# CurrentSense.net
KiCad netlist of a schematic drawn in Altium Designer
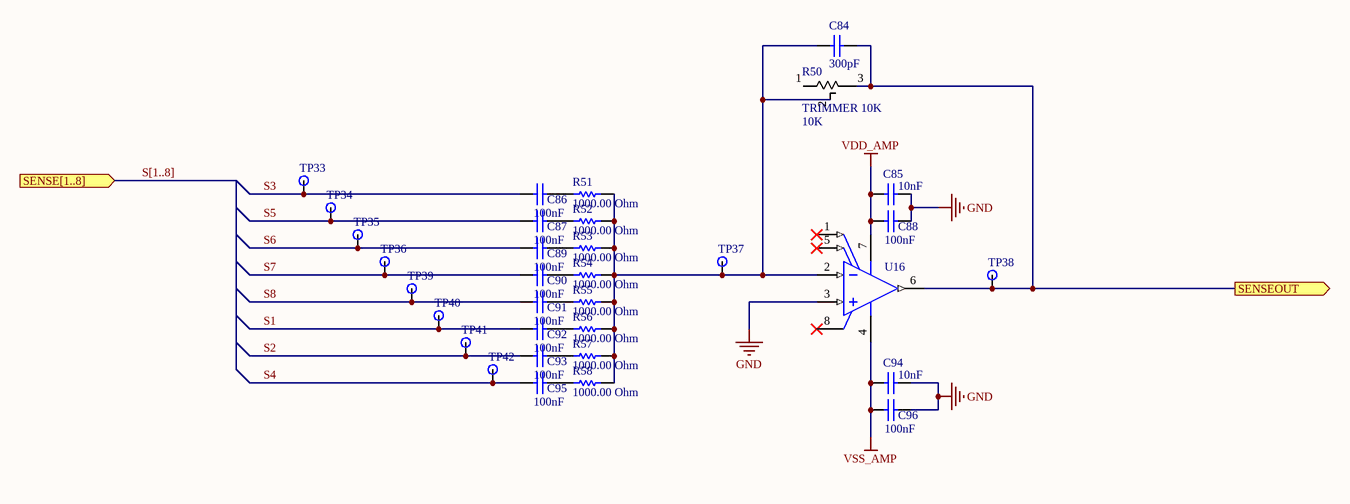
[diagram p0: CurrentSense.SchDoc]

(export (version "E")
  (design (tool "Eeschema 10.0.6"))
  (components
    (comp (ref "C84")
      (value "300pF")
      (footprint "CAPC0603(1608)100_N")
      (description "CAP 300pF 25V ±10% 0603 (1608 Metric) Thickness 1mm SMD")
      (fields (field (name "TOLERANCE") "Â±10%") (field (name "Comment") "CAP 300pF 25V 0603(1608)"))
      (libsource (lib "Altium Content Vault") (part "CMP-1035-01546-1"))
    )
    (comp (ref "C85")
      (value "10nF")
      (footprint "CAPC0603(1608)100_N")
      (description "CAP 10nF 25V ±10% 0603 (1608 Metric) Thickness 1mm SMD")
      (fields (field (name "TOLERANCE") "Â±10%") (field (name "Comment") "CAP 10nF 25V 0603(1608)"))
      (libsource (lib "Altium Content Vault") (part "CMP-1035-02317-1"))
    )
    (comp (ref "C86")
      (value "100nF")
      (footprint "CAPC0603(1608)100_M")
      (description "CAP 100nF 25V ±10% 0603 (1608 Metric) Thickness 1mm SMD")
      (fields (field (name "TOLERANCE") "Â±10%") (field (name "Comment") "CAP 100nF 25V 0603(1608)"))
      (libsource (lib "Altium Content Vault") (part "CMP-1035-02588-1"))
    )
    (comp (ref "C87")
      (value "100nF")
      (footprint "CAPC0603(1608)100_M")
      (description "CAP 100nF 25V ±10% 0603 (1608 Metric) Thickness 1mm SMD")
      (fields (field (name "TOLERANCE") "Â±10%") (field (name "Comment") "CAP 100nF 25V 0603(1608)"))
      (libsource (lib "Altium Content Vault") (part "CMP-1035-02588-1"))
    )
    (comp (ref "C88")
      (value "100nF")
      (footprint "CAPC0603(1608)100_M")
      (description "CAP 100nF 25V ±10% 0603 (1608 Metric) Thickness 1mm SMD")
      (fields (field (name "TOLERANCE") "Â±10%") (field (name "Comment") "CAP 100nF 25V 0603(1608)"))
      (libsource (lib "Altium Content Vault") (part "CMP-1035-02588-1"))
    )
    (comp (ref "C89")
      (value "100nF")
      (footprint "CAPC0603(1608)100_M")
      (description "CAP 100nF 25V ±10% 0603 (1608 Metric) Thickness 1mm SMD")
      (fields (field (name "TOLERANCE") "Â±10%") (field (name "Comment") "CAP 100nF 25V 0603(1608)"))
      (libsource (lib "Altium Content Vault") (part "CMP-1035-02588-1"))
    )
    (comp (ref "C90")
      (value "100nF")
      (footprint "CAPC0603(1608)100_M")
      (description "CAP 100nF 25V ±10% 0603 (1608 Metric) Thickness 1mm SMD")
      (fields (field (name "TOLERANCE") "Â±10%") (field (name "Comment") "CAP 100nF 25V 0603(1608)"))
      (libsource (lib "Altium Content Vault") (part "CMP-1035-02588-1"))
    )
    (comp (ref "C91")
      (value "100nF")
      (footprint "CAPC0603(1608)100_M")
      (description "CAP 100nF 25V ±10% 0603 (1608 Metric) Thickness 1mm SMD")
      (fields (field (name "TOLERANCE") "Â±10%") (field (name "Comment") "CAP 100nF 25V 0603(1608)"))
      (libsource (lib "Altium Content Vault") (part "CMP-1035-02588-1"))
    )
    (comp (ref "C92")
      (value "100nF")
      (footprint "CAPC0603(1608)100_M")
      (description "CAP 100nF 25V ±10% 0603 (1608 Metric) Thickness 1mm SMD")
      (fields (field (name "TOLERANCE") "Â±10%") (field (name "Comment") "CAP 100nF 25V 0603(1608)"))
      (libsource (lib "Altium Content Vault") (part "CMP-1035-02588-1"))
    )
    (comp (ref "C93")
      (value "100nF")
      (footprint "CAPC0603(1608)100_M")
      (description "CAP 100nF 25V ±10% 0603 (1608 Metric) Thickness 1mm SMD")
      (fields (field (name "TOLERANCE") "Â±10%") (field (name "Comment") "CAP 100nF 25V 0603(1608)"))
      (libsource (lib "Altium Content Vault") (part "CMP-1035-02588-1"))
    )
    (comp (ref "C94")
      (value "10nF")
      (footprint "CAPC0603(1608)100_N")
      (description "CAP 10nF 25V ±10% 0603 (1608 Metric) Thickness 1mm SMD")
      (fields (field (name "TOLERANCE") "Â±10%") (field (name "Comment") "CAP 10nF 25V 0603(1608)"))
      (libsource (lib "Altium Content Vault") (part "CMP-1035-02317-1"))
    )
    (comp (ref "C95")
      (value "100nF")
      (footprint "CAPC0603(1608)100_M")
      (description "CAP 100nF 25V ±10% 0603 (1608 Metric) Thickness 1mm SMD")
      (fields (field (name "TOLERANCE") "Â±10%") (field (name "Comment") "CAP 100nF 25V 0603(1608)"))
      (libsource (lib "Altium Content Vault") (part "CMP-1035-02588-1"))
    )
    (comp (ref "C96")
      (value "100nF")
      (footprint "CAPC0603(1608)100_M")
      (description "CAP 100nF 25V ±10% 0603 (1608 Metric) Thickness 1mm SMD")
      (fields (field (name "TOLERANCE") "Â±10%") (field (name "Comment") "CAP 100nF 25V 0603(1608)"))
      (libsource (lib "Altium Content Vault") (part "CMP-1035-02588-1"))
    )
    (comp (ref "R50")
      (value "TRIMMER 10K")
      (footprint "TRIMMER 10K")
      (description "TRIMMER 10K OHM 0.5W TH")
      (fields
        (field (name "MANUFACTURER") "TE Connectivity Passive Product")
        (field (name "MANUFACTURER PART NUMBER") "1-1623849-0")
        (field (name "ALTIUM_VALUE") "10K")
        (field (name "PUBLISHER") "Altium Limited")
      )
      (libsource (lib "AnserEMT") (part "TRIMMER 10K"))
    )
    (comp (ref "R51")
      (value "1000.00 Ohm")
      (footprint "RESC0603(1608)_L")
      (description "1K 0.1W 5% 0603 (1608 Metric)  SMD")
      (fields (field (name "TOLERANCE") "5 %") (field (name "POWER") "0.1 W"))
      (libsource (lib "Altium Content Vault") (part "CMP-1012-00074-1"))
    )
    (comp (ref "R52")
      (value "1000.00 Ohm")
      (footprint "RESC0603(1608)_L")
      (description "1K 0.1W 5% 0603 (1608 Metric)  SMD")
      (fields (field (name "TOLERANCE") "5 %") (field (name "POWER") "0.1 W"))
      (libsource (lib "Altium Content Vault") (part "CMP-1012-00074-1"))
    )
    (comp (ref "R53")
      (value "1000.00 Ohm")
      (footprint "RESC0603(1608)_L")
      (description "1K 0.1W 5% 0603 (1608 Metric)  SMD")
      (fields (field (name "TOLERANCE") "5 %") (field (name "POWER") "0.1 W"))
      (libsource (lib "Altium Content Vault") (part "CMP-1012-00074-1"))
    )
    (comp (ref "R54")
      (value "1000.00 Ohm")
      (footprint "RESC0603(1608)_L")
      (description "1K 0.1W 5% 0603 (1608 Metric)  SMD")
      (fields (field (name "TOLERANCE") "5 %") (field (name "POWER") "0.1 W"))
      (libsource (lib "Altium Content Vault") (part "CMP-1012-00074-1"))
    )
    (comp (ref "R55")
      (value "1000.00 Ohm")
      (footprint "RESC0603(1608)_L")
      (description "1K 0.1W 5% 0603 (1608 Metric)  SMD")
      (fields (field (name "TOLERANCE") "5 %") (field (name "POWER") "0.1 W"))
      (libsource (lib "Altium Content Vault") (part "CMP-1012-00074-1"))
    )
    (comp (ref "R56")
      (value "1000.00 Ohm")
      (footprint "RESC0603(1608)_L")
      (description "1K 0.1W 5% 0603 (1608 Metric)  SMD")
      (fields (field (name "TOLERANCE") "5 %") (field (name "POWER") "0.1 W"))
      (libsource (lib "Altium Content Vault") (part "CMP-1012-00074-1"))
    )
    (comp (ref "R57")
      (value "1000.00 Ohm")
      (footprint "RESC0603(1608)_L")
      (description "1K 0.1W 5% 0603 (1608 Metric)  SMD")
      (fields (field (name "TOLERANCE") "5 %") (field (name "POWER") "0.1 W"))
      (libsource (lib "Altium Content Vault") (part "CMP-1012-00074-1"))
    )
    (comp (ref "R58")
      (value "1000.00 Ohm")
      (footprint "RESC0603(1608)_L")
      (description "1K 0.1W 5% 0603 (1608 Metric)  SMD")
      (fields (field (name "TOLERANCE") "5 %") (field (name "POWER") "0.1 W"))
      (libsource (lib "Altium Content Vault") (part "CMP-1012-00074-1"))
    )
    (comp (ref "TP33")
      (value "Testpoint")
      (footprint "0603 PROBE PAD")
      (description "0.063\" x 0.031\" x 0.045\" (1.60mm x 0.80mm x 1.15mm)")
      (libsource (lib "testpoint") (part "Testpoint"))
    )
    (comp (ref "TP34")
      (value "Testpoint")
      (footprint "0603 PROBE PAD")
      (description "0.063\" x 0.031\" x 0.045\" (1.60mm x 0.80mm x 1.15mm)")
      (libsource (lib "testpoint") (part "Testpoint"))
    )
    (comp (ref "TP35")
      (value "Testpoint")
      (footprint "0603 PROBE PAD")
      (description "0.063\" x 0.031\" x 0.045\" (1.60mm x 0.80mm x 1.15mm)")
      (libsource (lib "testpoint") (part "Testpoint"))
    )
    (comp (ref "TP36")
      (value "Testpoint")
      (footprint "0603 PROBE PAD")
      (description "0.063\" x 0.031\" x 0.045\" (1.60mm x 0.80mm x 1.15mm)")
      (libsource (lib "testpoint") (part "Testpoint"))
    )
    (comp (ref "TP37")
      (value "Testpoint")
      (footprint "0603 PROBE PAD")
      (description "0.063\" x 0.031\" x 0.045\" (1.60mm x 0.80mm x 1.15mm)")
      (libsource (lib "testpoint") (part "Testpoint"))
    )
    (comp (ref "TP38")
      (value "Testpoint")
      (footprint "0603 PROBE PAD")
      (description "0.063\" x 0.031\" x 0.045\" (1.60mm x 0.80mm x 1.15mm)")
      (libsource (lib "testpoint") (part "Testpoint"))
    )
    (comp (ref "TP39")
      (value "Testpoint")
      (footprint "0603 PROBE PAD")
      (description "0.063\" x 0.031\" x 0.045\" (1.60mm x 0.80mm x 1.15mm)")
      (libsource (lib "testpoint") (part "Testpoint"))
    )
    (comp (ref "TP40")
      (value "Testpoint")
      (footprint "0603 PROBE PAD")
      (description "0.063\" x 0.031\" x 0.045\" (1.60mm x 0.80mm x 1.15mm)")
      (libsource (lib "testpoint") (part "Testpoint"))
    )
    (comp (ref "TP41")
      (value "Testpoint")
      (footprint "0603 PROBE PAD")
      (description "0.063\" x 0.031\" x 0.045\" (1.60mm x 0.80mm x 1.15mm)")
      (libsource (lib "testpoint") (part "Testpoint"))
    )
    (comp (ref "TP42")
      (value "Testpoint")
      (footprint "0603 PROBE PAD")
      (description "0.063\" x 0.031\" x 0.045\" (1.60mm x 0.80mm x 1.15mm)")
      (libsource (lib "testpoint") (part "Testpoint"))
    )
    (comp (ref "U16")
      (value "TL081CDG4")
      (footprint "TI-D8_N")
      (fields
        (field (name "MANUFACTURER") "Texas Instruments")
        (field (name "MANUFACTURER PART NUMBER") "TL081CDR")
      )
      (libsource (lib "Altium Content Vault") (part "CMP-0017-00506-1"))
    )
  )
  (nets
    (net (code "1") (name "/S1") (class "Default")
      (node (ref "C92") (pin "2") (pinfunction "2_2") (pintype "passive"))
      (node (ref "TP40") (pin "0") (pintype "passive"))
    )
    (net (code "2") (name "/S2") (class "Default")
      (node (ref "C93") (pin "2") (pinfunction "2_2") (pintype "passive"))
      (node (ref "TP41") (pin "0") (pintype "passive"))
    )
    (net (code "3") (name "/S3") (class "Default")
      (node (ref "C86") (pin "2") (pinfunction "2_2") (pintype "passive"))
      (node (ref "TP33") (pin "0") (pintype "passive"))
    )
    (net (code "4") (name "/S4") (class "Default")
      (node (ref "C95") (pin "2") (pinfunction "2_2") (pintype "passive"))
      (node (ref "TP42") (pin "0") (pintype "passive"))
    )
    (net (code "5") (name "/S5") (class "Default")
      (node (ref "C87") (pin "2") (pinfunction "2_2") (pintype "passive"))
      (node (ref "TP34") (pin "0") (pintype "passive"))
    )
    (net (code "6") (name "/S6") (class "Default")
      (node (ref "C89") (pin "2") (pinfunction "2_2") (pintype "passive"))
      (node (ref "TP35") (pin "0") (pintype "passive"))
    )
    (net (code "7") (name "/S7") (class "Default")
      (node (ref "C90") (pin "2") (pinfunction "2_2") (pintype "passive"))
      (node (ref "TP36") (pin "0") (pintype "passive"))
    )
    (net (code "8") (name "/S8") (class "Default")
      (node (ref "C91") (pin "2") (pinfunction "2_2") (pintype "passive"))
      (node (ref "TP39") (pin "0") (pintype "passive"))
    )
    (net (code "9") (name "/SENSEOUT") (class "Default")
      (node (ref "C84") (pin "1") (pinfunction "1_1") (pintype "passive"))
      (node (ref "R50") (pin "3") (pinfunction "3_3") (pintype "passive"))
      (node (ref "TP38") (pin "0") (pintype "passive"))
      (node (ref "U16") (pin "6") (pinfunction "OUT_6") (pintype "output"))
    )
    (net (code "11") (name "GND") (class "Default")
      (node (ref "C85") (pin "2") (pinfunction "2_2") (pintype "passive"))
      (node (ref "C88") (pin "1") (pinfunction "1_1") (pintype "passive"))
      (node (ref "C94") (pin "2") (pinfunction "2_2") (pintype "passive"))
      (node (ref "C96") (pin "1") (pinfunction "1_1") (pintype "passive"))
      (node (ref "U16") (pin "3") (pinfunction "IN+_3") (pintype "input"))
    )
    (net (code "12") (name "Net-(C86-Pad1)") (class "Default")
      (node (ref "C86") (pin "1") (pinfunction "1_1") (pintype "passive"))
      (node (ref "R51") (pin "2") (pinfunction "2_2") (pintype "passive"))
    )
    (net (code "13") (name "Net-(C87-Pad1)") (class "Default")
      (node (ref "C87") (pin "1") (pinfunction "1_1") (pintype "passive"))
      (node (ref "R52") (pin "2") (pinfunction "2_2") (pintype "passive"))
    )
    (net (code "14") (name "Net-(C89-Pad1)") (class "Default")
      (node (ref "C89") (pin "1") (pinfunction "1_1") (pintype "passive"))
      (node (ref "R53") (pin "2") (pinfunction "2_2") (pintype "passive"))
    )
    (net (code "15") (name "Net-(C90-Pad1)") (class "Default")
      (node (ref "C90") (pin "1") (pinfunction "1_1") (pintype "passive"))
      (node (ref "R54") (pin "2") (pinfunction "2_2") (pintype "passive"))
    )
    (net (code "16") (name "Net-(C91-Pad1)") (class "Default")
      (node (ref "C91") (pin "1") (pinfunction "1_1") (pintype "passive"))
      (node (ref "R55") (pin "2") (pinfunction "2_2") (pintype "passive"))
    )
    (net (code "17") (name "Net-(C92-Pad1)") (class "Default")
      (node (ref "C92") (pin "1") (pinfunction "1_1") (pintype "passive"))
      (node (ref "R56") (pin "2") (pinfunction "2_2") (pintype "passive"))
    )
    (net (code "18") (name "Net-(C93-Pad1)") (class "Default")
      (node (ref "C93") (pin "1") (pinfunction "1_1") (pintype "passive"))
      (node (ref "R57") (pin "2") (pinfunction "2_2") (pintype "passive"))
    )
    (net (code "19") (name "Net-(C95-Pad1)") (class "Default")
      (node (ref "C95") (pin "1") (pinfunction "1_1") (pintype "passive"))
      (node (ref "R58") (pin "2") (pinfunction "2_2") (pintype "passive"))
    )
    (net (code "20") (name "Net-(U16-IN-)") (class "Default")
      (node (ref "C84") (pin "2") (pinfunction "2_2") (pintype "passive"))
      (node (ref "R50") (pin "2") (pinfunction "2_2") (pintype "passive"))
      (node (ref "R51") (pin "1") (pinfunction "1_1") (pintype "passive"))
      (node (ref "R52") (pin "1") (pinfunction "1_1") (pintype "passive"))
      (node (ref "R53") (pin "1") (pinfunction "1_1") (pintype "passive"))
      (node (ref "R54") (pin "1") (pinfunction "1_1") (pintype "passive"))
      (node (ref "R55") (pin "1") (pinfunction "1_1") (pintype "passive"))
      (node (ref "R56") (pin "1") (pinfunction "1_1") (pintype "passive"))
      (node (ref "R57") (pin "1") (pinfunction "1_1") (pintype "passive"))
      (node (ref "R58") (pin "1") (pinfunction "1_1") (pintype "passive"))
      (node (ref "TP37") (pin "0") (pintype "passive"))
      (node (ref "U16") (pin "2") (pinfunction "IN-_2") (pintype "input"))
    )
    (net (code "21") (name "VDD_AMP") (class "Default")
      (node (ref "C85") (pin "1") (pinfunction "1_1") (pintype "passive"))
      (node (ref "C88") (pin "2") (pinfunction "2_2") (pintype "passive"))
      (node (ref "U16") (pin "7") (pinfunction "VCC+_7") (pintype "power_in"))
    )
    (net (code "22") (name "VSS_AMP") (class "Default")
      (node (ref "C94") (pin "1") (pinfunction "1_1") (pintype "passive"))
      (node (ref "C96") (pin "2") (pinfunction "2_2") (pintype "passive"))
      (node (ref "U16") (pin "4") (pinfunction "VCC-_4") (pintype "power_in"))
    )
    (net (code "23") (name "unconnected-(R50-Pad1)") (class "Default")
      (node (ref "R50") (pin "1") (pinfunction "1_1") (pintype "passive"))
    )
    (net (code "24") (name "unconnected-(U16-NC-Pad8)") (class "Default")
      (node (ref "U16") (pin "8") (pinfunction "NC_8") (pintype "passive+no_connect"))
    )
    (net (code "25") (name "unconnected-(U16-OFFSET_N1-Pad1)") (class "Default")
      (node (ref "U16") (pin "1") (pinfunction "OFFSET_N1_1") (pintype "input+no_connect"))
    )
    (net (code "26") (name "unconnected-(U16-OFFSET_N2-Pad5)") (class "Default")
      (node (ref "U16") (pin "5") (pinfunction "OFFSET_N2_5") (pintype "input+no_connect"))
    )
  )
)
